# RX_Schematics.net
KiCad netlist of a schematic drawn in Altium Designer
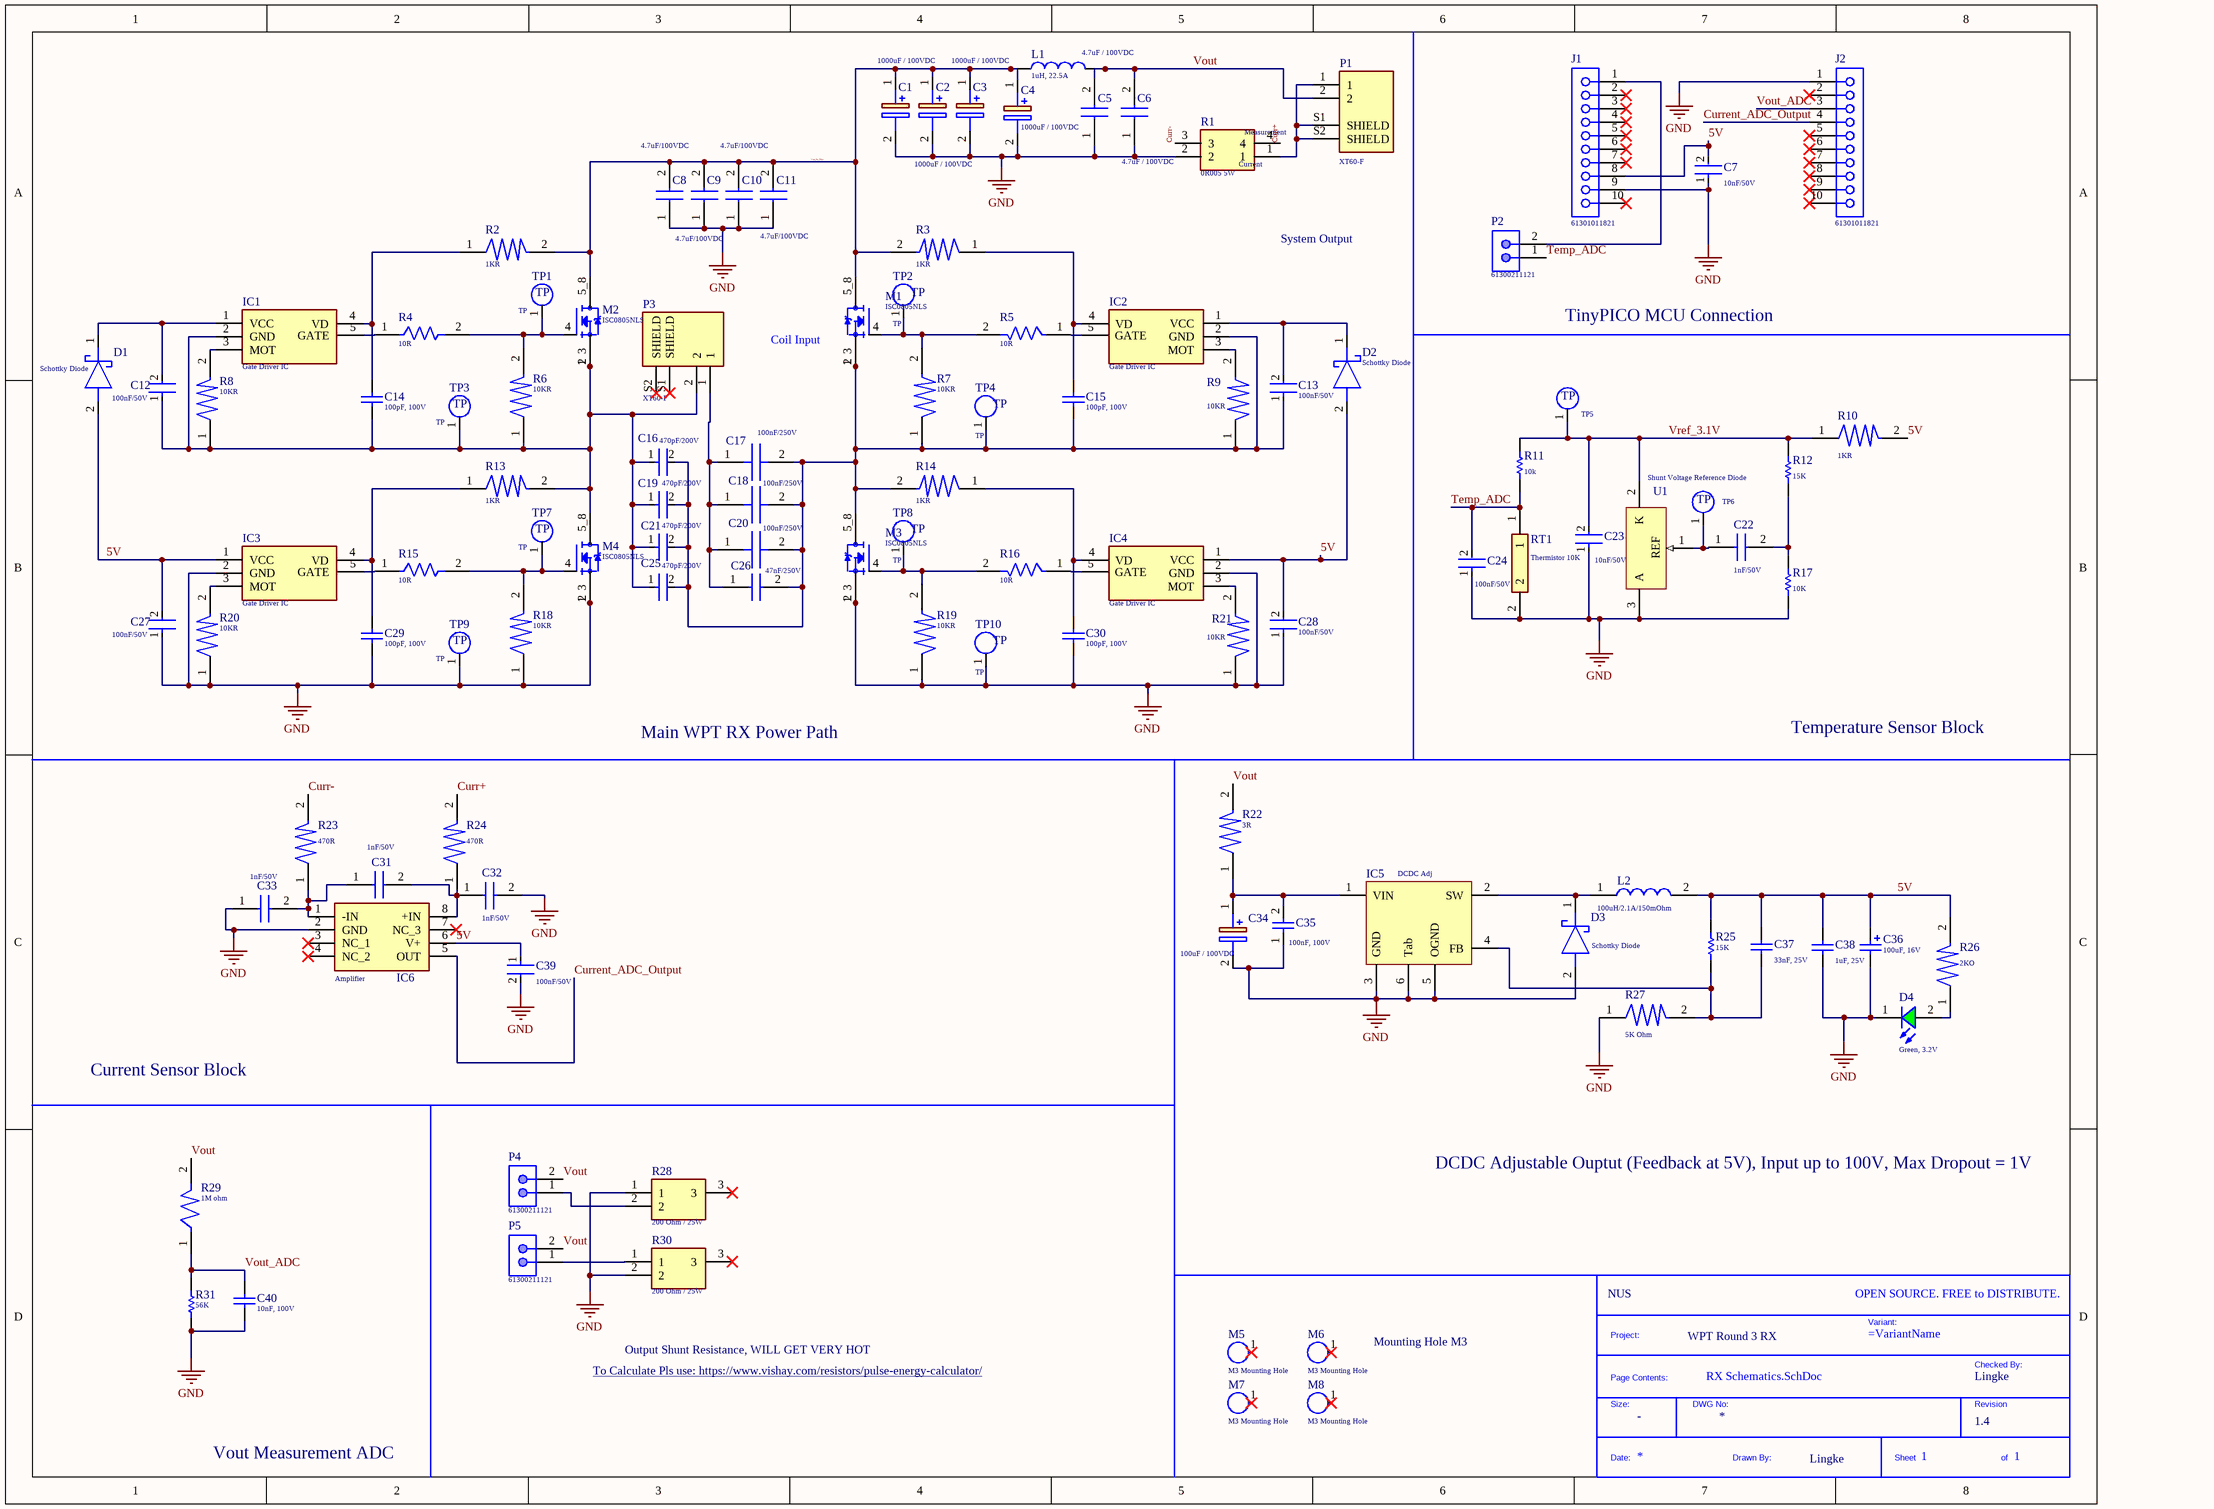
[diagram p0: RX Schematics.SchDoc]

(export (version "E")
  (design (tool "Eeschema 10.0.6"))
  (components
    (comp (ref "*1")
      (value "Title_Block")
      (description "Standard Title Block.")
      (fields
        (field (name "PROJECT NAME") "WPT Round 3 RX")
        (field (name "COMPANY") "NUS")
        (field (name "DRAWN BY") "Lingke")
        (field (name "REVISION") "1.4")
        (field (name "DWG NO") "*")
        (field (name "SIZE") "-")
        (field (name "CHECKED BY") "Lingke")
      )
      (libsource (lib "WPT NUS") (part "Title_Block"))
    )
    (comp (ref "C1")
      (value "1000uF / 100VDC")
      (footprint "CAPPRD750W80D1850H4200")
      (description "Capacitor Polarised")
      (fields
        (field (name "MANUFACTURER_PART_NUMBER") "UPW2A102MHD")
        (field (name "MOUSER PART NUMBER") "647-UPW2A102MHD")
      )
      (libsource (lib "WPT NUS") (part "UPW2A102MHD"))
    )
    (comp (ref "C2")
      (value "1000uF / 100VDC")
      (footprint "CAPPRD750W80D1850H4200")
      (description "Capacitor Polarised")
      (fields
        (field (name "MANUFACTURER_PART_NUMBER") "UPW2A102MHD")
        (field (name "MOUSER PART NUMBER") "647-UPW2A102MHD")
      )
      (libsource (lib "WPT NUS") (part "UPW2A102MHD"))
    )
    (comp (ref "C3")
      (value "1000uF / 100VDC")
      (footprint "CAPPRD750W80D1850H4200")
      (description "Capacitor Polarised")
      (fields
        (field (name "MANUFACTURER_PART_NUMBER") "UPW2A102MHD")
        (field (name "MOUSER PART NUMBER") "647-UPW2A102MHD")
      )
      (libsource (lib "WPT NUS") (part "UPW2A102MHD"))
    )
    (comp (ref "C4")
      (value "1000uF / 100VDC")
      (footprint "CAPPRD750W80D1850H4200")
      (description "Capacitor Polarised")
      (fields
        (field (name "MANUFACTURER_PART_NUMBER") "UPW2A102MHD")
        (field (name "MOUSER PART NUMBER") "647-UPW2A102MHD")
      )
      (libsource (lib "WPT NUS") (part "UPW2A102MHD"))
    )
    (comp (ref "C5")
      (value "4.7uF / 100VDC")
      (footprint "CAPC3225X280N")
      (description "Capacitor")
      (fields (field (name "MANUFACTURER_PART_NUMBER") "CL32B475KCVZNWE"))
      (libsource (lib "WPT NUS") (part "CL32B475KCVZNWE"))
    )
    (comp (ref "C6")
      (value "4.7uF / 100VDC")
      (footprint "CAPC3225X280N")
      (description "Capacitor")
      (fields (field (name "MANUFACTURER_PART_NUMBER") "CL32B475KCVZNWE"))
      (libsource (lib "WPT NUS") (part "CL32B475KCVZNWE"))
    )
    (comp (ref "C7")
      (value "10nF/50V")
      (footprint "0805 Capacitor")
      (libsource (lib "Symbol Library") (part "885012207092"))
    )
    (comp (ref "C8")
      (value "4.7uF/100VDC")
      (footprint "CAPC3225X280N")
      (fields
        (field (name "MOUSER2 PART NUMBER") "810-CNC6P1X7R2A475K2")
        (field (name "MANUFACTURER_PART_NUMBER") "CNC6P1X7R2A475K250AE")
      )
      (libsource (lib "WPT NUS") (part "CNC6P1X7R2A475K250AE"))
    )
    (comp (ref "C9")
      (value "4.7uF/100VDC")
      (footprint "CAPC3225X280N")
      (fields
        (field (name "MOUSER2 PART NUMBER") "810-CNC6P1X7R2A475K2")
        (field (name "MANUFACTURER_PART_NUMBER") "CNC6P1X7R2A475K250AE")
      )
      (libsource (lib "WPT NUS") (part "CNC6P1X7R2A475K250AE"))
    )
    (comp (ref "C10")
      (value "4.7uF/100VDC")
      (footprint "CAPC3225X280N")
      (fields
        (field (name "MOUSER2 PART NUMBER") "810-CNC6P1X7R2A475K2")
        (field (name "MANUFACTURER_PART_NUMBER") "CNC6P1X7R2A475K250AE")
      )
      (libsource (lib "WPT NUS") (part "CNC6P1X7R2A475K250AE"))
    )
    (comp (ref "C11")
      (value "4.7uF/100VDC")
      (footprint "CAPC3225X280N")
      (fields
        (field (name "MOUSER2 PART NUMBER") "810-CNC6P1X7R2A475K2")
        (field (name "MANUFACTURER_PART_NUMBER") "CNC6P1X7R2A475K250AE")
      )
      (libsource (lib "WPT NUS") (part "CNC6P1X7R2A475K250AE"))
    )
    (comp (ref "C12")
      (value "100nF/50V")
      (footprint "0805 Capacitor")
      (libsource (lib "WPT NUS") (part "885012207098"))
    )
    (comp (ref "C13")
      (value "100nF/50V")
      (footprint "0805 Capacitor")
      (libsource (lib "WPT NUS") (part "885012207098"))
    )
    (comp (ref "C14")
      (value "100pF, 100V")
      (footprint "WCAP-CSGP_0805_H=0.6mm_Reflow")
      (description "WCAP-CSGP Multilayer Ceramic Chip Capacitor, General Purpose, size 0805, NP0, 100pF, 100V")
      (fields
        (field (name "MANUFACTURER PART NUMBER") "885012007082")
        (field (name "MANUFACTURER") "Wurth Elektronik")
      )
      (libsource (lib "Altium_WCAP-CSGP (rev21d)") (part "885012007082"))
    )
    (comp (ref "C15")
      (value "100pF, 100V")
      (footprint "WCAP-CSGP_0805_H=0.6mm_Reflow")
      (description "WCAP-CSGP Multilayer Ceramic Chip Capacitor, General Purpose, size 0805, NP0, 100pF, 100V")
      (fields
        (field (name "MANUFACTURER PART NUMBER") "885012007082")
        (field (name "MANUFACTURER") "Wurth Elektronik")
      )
      (libsource (lib "Altium_WCAP-CSGP (rev21d)") (part "885012007082"))
    )
    (comp (ref "C16")
      (value "470pF/200V")
      (footprint "FP-C1206C-EB-MFG")
      (description "CAP CER 470PF 200V 10% NP0 1206")
      (fields
        (field (name "OCTOPART") "https://octopart.com/c1206c471k2gactu-kemet-3658280")
        (field (name "TOLERANCE") "0.1")
      )
      (libsource (lib "WPT NUS") (part "C1206C471K2GACTU"))
    )
    (comp (ref "C17")
      (value "100nF/250V")
      (footprint "CAPC4532X220N")
      (fields (field (name "MANUFACTURER_PART_NUMBER") "C1812C104JAGACAUTO"))
      (libsource (lib "WPT NUS") (part "C1812C104JAGACAUTO"))
    )
    (comp (ref "C18")
      (value "100nF/250V")
      (footprint "CAPC4532X220N")
      (fields (field (name "MANUFACTURER_PART_NUMBER") "C1812C104JAGACAUTO"))
      (libsource (lib "WPT NUS") (part "C1812C104JAGACAUTO"))
    )
    (comp (ref "C19")
      (value "470pF/200V")
      (footprint "FP-C1206C-EB-MFG")
      (description "CAP CER 470PF 200V 10% NP0 1206")
      (fields
        (field (name "OCTOPART") "https://octopart.com/c1206c471k2gactu-kemet-3658280")
        (field (name "TOLERANCE") "0.1")
      )
      (libsource (lib "WPT NUS") (part "C1206C471K2GACTU"))
    )
    (comp (ref "C20")
      (value "100nF/250V")
      (footprint "CAPC4532X220N")
      (fields (field (name "MANUFACTURER_PART_NUMBER") "C1812C104JAGACAUTO"))
      (libsource (lib "WPT NUS") (part "C1812C104JAGACAUTO"))
    )
    (comp (ref "C21")
      (value "470pF/200V")
      (footprint "FP-C1206C-EB-MFG")
      (description "CAP CER 470PF 200V 10% NP0 1206")
      (fields
        (field (name "OCTOPART") "https://octopart.com/c1206c471k2gactu-kemet-3658280")
        (field (name "TOLERANCE") "0.1")
      )
      (libsource (lib "WPT NUS") (part "C1206C471K2GACTU"))
    )
    (comp (ref "C22")
      (value "1nF/50V")
      (footprint "SamacSys:CAPC2012X90N")
      (fields (field (name "MANUFACTURER_PART_NUMBER") "885012207086"))
      (libsource (lib "Symbol Library") (part "885012207086"))
    )
    (comp (ref "C23")
      (value "10nF/50V")
      (footprint "0805 Capacitor")
      (libsource (lib "Symbol Library") (part "885012207092"))
    )
    (comp (ref "C24")
      (value "100nF/50V")
      (footprint "0805 Capacitor")
      (libsource (lib "Symbol Library") (part "885012207098"))
    )
    (comp (ref "C25")
      (value "470pF/200V")
      (footprint "FP-C1206C-EB-MFG")
      (description "CAP CER 470PF 200V 10% NP0 1206")
      (fields
        (field (name "OCTOPART") "https://octopart.com/c1206c471k2gactu-kemet-3658280")
        (field (name "TOLERANCE") "0.1")
      )
      (libsource (lib "WPT NUS") (part "C1206C471K2GACTU"))
    )
    (comp (ref "C26")
      (value "47nF/250V")
      (footprint "CAPC4532X350N")
      (description "Capacitor\r\n47nF/250V \r\nC0G")
      (fields (field (name "MANUFACTURER_PART_NUMBER") "C4532C0G2E473J320KA"))
      (libsource (lib "WPT NUS") (part "C4532C0G2E473J320KA"))
    )
    (comp (ref "C27")
      (value "100nF/50V")
      (footprint "0805 Capacitor")
      (libsource (lib "WPT NUS") (part "885012207098"))
    )
    (comp (ref "C28")
      (value "100nF/50V")
      (footprint "0805 Capacitor")
      (libsource (lib "WPT NUS") (part "885012207098"))
    )
    (comp (ref "C29")
      (value "100pF, 100V")
      (footprint "WCAP-CSGP_0805_H=0.6mm_Reflow")
      (description "WCAP-CSGP Multilayer Ceramic Chip Capacitor, General Purpose, size 0805, NP0, 100pF, 100V")
      (fields
        (field (name "MANUFACTURER PART NUMBER") "885012007082")
        (field (name "MANUFACTURER") "Wurth Elektronik")
      )
      (libsource (lib "Altium_WCAP-CSGP (rev21d)") (part "885012007082"))
    )
    (comp (ref "C30")
      (value "100pF, 100V")
      (footprint "WCAP-CSGP_0805_H=0.6mm_Reflow")
      (description "WCAP-CSGP Multilayer Ceramic Chip Capacitor, General Purpose, size 0805, NP0, 100pF, 100V")
      (fields
        (field (name "MANUFACTURER PART NUMBER") "885012007082")
        (field (name "MANUFACTURER") "Wurth Elektronik")
      )
      (libsource (lib "Altium_WCAP-CSGP (rev21d)") (part "885012007082"))
    )
    (comp (ref "C31")
      (value "1nF/50V")
      (footprint "SamacSys:CAPC2012X90N")
      (fields (field (name "MANUFACTURER_PART_NUMBER") "885012207086"))
      (libsource (lib "Symbol Library") (part "885012207086"))
    )
    (comp (ref "C32")
      (value "1nF/50V")
      (footprint "SamacSys:CAPC2012X90N")
      (fields (field (name "MANUFACTURER_PART_NUMBER") "885012207086"))
      (libsource (lib "Symbol Library") (part "885012207086"))
    )
    (comp (ref "C33")
      (value "1nF/50V")
      (footprint "SamacSys:CAPC2012X90N")
      (fields (field (name "MANUFACTURER_PART_NUMBER") "885012207086"))
      (libsource (lib "Symbol Library") (part "885012207086"))
    )
    (comp (ref "C34")
      (value "100uF / 100VDC")
      (footprint "CAPPRD500W60D1000H2200")
      (description "Capacitor Polarised")
      (fields
        (field (name "MANUFACTURER_PART_NUMBER") "ESH107M100AH4AA")
        (field (name "MOUSER PART NUMBER") "80-ESH107M100AH4AA")
      )
      (libsource (lib "WPT NUS") (part "ESH107M100AH4AA"))
    )
    (comp (ref "C35")
      (value "100nF, 100V")
      (footprint "WCAP-CSGP_0805_H=1.25mm")
      (description "WCAP-CSGP Multilayer Ceramic Chip Capacitor, General Purpose, size 0805, X7R, 100nF, 100V")
      (fields
        (field (name "MANUFACTURER PART NUMBER") "885012207128")
        (field (name "MANUFACTURER") "Wurth Elektronik")
      )
      (libsource (lib "Symbol Library") (part "885012207128"))
    )
    (comp (ref "C36")
      (value "100uF, 16V")
      (footprint "WCAP-ASLI_D6.3H5.5")
      (description "WCAP-ASLI Aluminum Electrolytic Capacitor, V-Chip, SMT, D6.3xH5.5mm, 100uF, 16V")
      (fields
        (field (name "MANUFACTURER PART NUMBER") "865080343009")
        (field (name "MANUFACTURER") "Wurth Elektronik")
      )
      (libsource (lib "Altium_WCAP-ASLI (rev20b) (1)") (part "865080343009"))
    )
    (comp (ref "C37")
      (value "33nF, 25V")
      (footprint "WCAP-CSGP_0805_H=0.8mm_Reflow")
      (description "WCAP-CSGP Multilayer Ceramic Chip Capacitor, General Purpose, size 0805, X7R, 33nF, 25V")
      (fields
        (field (name "MANUFACTURER PART NUMBER") "885012207069")
        (field (name "MANUFACTURER") "Wurth Elektronik")
      )
      (libsource (lib "Altium_WCAP-CSGP (rev21d)") (part "885012207069"))
    )
    (comp (ref "C38")
      (value "1uF, 25V")
      (footprint "WCAP-CSGP_0805_H=1.25mm")
      (description "WCAP-CSGP Multilayer Ceramic Chip Capacitor, General Purpose, size 0805, X7R, 1uF, 25V")
      (fields
        (field (name "MANUFACTURER PART NUMBER") "885012207078")
        (field (name "MANUFACTURER") "Wurth Elektronik")
      )
      (libsource (lib "Altium_WCAP-CSGP (rev21d)") (part "885012207078"))
    )
    (comp (ref "C39")
      (value "100nF/50V")
      (footprint "0805 Capacitor")
      (libsource (lib "Symbol Library") (part "885012207098"))
    )
    (comp (ref "C40")
      (value "10nF, 100V")
      (footprint "WCAP-CSGP_0805_H=0.8mm_Reflow")
      (description "WCAP-CSGP Multilayer Ceramic Chip Capacitor, General Purpose, size 0805, X7R, 10nF, 100V")
      (fields
        (field (name "MANUFACTURER PART NUMBER") "885012207122")
        (field (name "MANUFACTURER") "Wurth Elektronik")
      )
      (libsource (lib "Altium_WCAP-CSGP (rev21d)") (part "885012207122"))
    )
    (comp (ref "D1")
      (value "Schottky Diode")
      (footprint "RB400VAM50TR")
      (fields
        (field (name "MOUSER2 PART NUMBER") "755-RB400VAM-50TR")
        (field (name "MANUFACTURER_PART_NUMBER") "RB400VAM-50TR")
      )
      (libsource (lib "WPT NUS") (part "RB400VAM-50TR"))
    )
    (comp (ref "D2")
      (value "Schottky Diode")
      (footprint "RB400VAM50TR")
      (fields
        (field (name "MOUSER2 PART NUMBER") "755-RB400VAM-50TR")
        (field (name "MANUFACTURER_PART_NUMBER") "RB400VAM-50TR")
      )
      (libsource (lib "") (part "RB400VAM-50TR_1"))
    )
    (comp (ref "D3")
      (value "Schottky Diode")
      (footprint "SamacSys:DIONM8059X265N")
      (fields (field (name "MANUFACTURER_PART_NUMBER") "S310") (field (name "MOUSER PART NUMBER") "512-S310"))
      (libsource (lib "Symbol Library") (part "S310"))
    )
    (comp (ref "D4")
      (value "Green, 3.2V")
      (footprint "WL-SMCW_0805")
      (description "WL-SMCW SMT Mono-color Chip LED Waterclear, size 0805, Green, 3.2V, 140deg")
      (fields (field (name "PART NUMBER") "150080GS75000") (field (name "PUBLISHER") "Wurth Elektronik"))
      (libsource (lib "Altium_WL-SMCW (rev20a)") (part "150080GS75000"))
    )
    (comp (ref "IC1")
      (value "Gate Driver IC")
      (footprint "SOT95P280X145-5N")
      (fields (field (name "MANUFACTURER_PART_NUMBER") "IR1161LTRPBF"))
      (libsource (lib "") (part "IR1161LTRPBF_1"))
    )
    (comp (ref "IC2")
      (value "Gate Driver IC")
      (footprint "SOT95P280X145-5N")
      (fields (field (name "MANUFACTURER_PART_NUMBER") "IR1161LTRPBF"))
      (libsource (lib "WPT NUS") (part "IR1161LTRPBF"))
    )
    (comp (ref "IC3")
      (value "Gate Driver IC")
      (footprint "SOT95P280X145-5N")
      (fields (field (name "MANUFACTURER_PART_NUMBER") "IR1161LTRPBF"))
      (libsource (lib "") (part "IR1161LTRPBF_1"))
    )
    (comp (ref "IC4")
      (value "Gate Driver IC")
      (footprint "SOT95P280X145-5N")
      (fields (field (name "MANUFACTURER_PART_NUMBER") "IR1161LTRPBF"))
      (libsource (lib "WPT NUS") (part "IR1161LTRPBF"))
    )
    (comp (ref "IC5")
      (value "DCDC Adj")
      (footprint "TO-263-5")
      (libsource (lib "Symbol Library") (part "XL7035E1"))
    )
    (comp (ref "IC6")
      (value "Amplifier")
      (footprint "SamacSys:SOIC127P600X175-8N")
      (description "Integrated Circuit Amplifier")
      (fields (field (name "MANUFACTURER_PART_NUMBER") "AD8215YRZ"))
      (libsource (lib "Symbol Library") (part "AD8215YRZ"))
    )
    (comp (ref "J1")
      (value "61301011821")
      (footprint "61301011821")
      (description "WR-PHD Socket Header, THT, pitch 2.54mm, Single Row, Vertical, 10p")
      (fields (field (name "MANUFACTURER") "Wurth Elektronik"))
      (libsource (lib "Altium_WR-PHD (rev20a)") (part "61301011821"))
    )
    (comp (ref "J2")
      (value "61301011821")
      (footprint "61301011821")
      (description "WR-PHD Socket Header, THT, pitch 2.54mm, Single Row, Vertical, 10p")
      (fields (field (name "MANUFACTURER") "Wurth Elektronik"))
      (libsource (lib "Altium_WR-PHD (rev20a)") (part "61301011821"))
    )
    (comp (ref "L1")
      (value "1uH, 22.5A")
      (footprint "7847227010")
      (description "WE-RCIS SMT Rod Core Inductor, 1uH, 22.5A")
      (fields
        (field (name "MANUFACTURER PART NUMBER") "7847227010")
        (field (name "MANUFACTURER") "Wurth Elektronik")
      )
      (libsource (lib "Altium_WE-RCIS (rev21a)") (part "7847227010"))
    )
    (comp (ref "L2")
      (value "100uH/2.1A/150mOhm")
      (footprint "SamacSys:INDPM125125X800N")
      (description "Inductor")
      (fields
        (field (name "MANUFACTURER_PART_NUMBER") "SRR1280-101M")
        (field (name "MOUSER PART NUMBER") "652-SRR1280-101M")
      )
      (libsource (lib "Symbol Library") (part "SRR1280-101M"))
    )
    (comp (ref "M1")
      (value "ISC0805NLS")
      (footprint "PG-TDSON-8")
      (description "N-Channel 100V 71A 72")
      (fields (field (name "MP") "BSC010NE2LSI"))
      (libsource (lib "Symbol Library") (part "ISC0805NLS"))
    )
    (comp (ref "M2")
      (value "ISC0805NLS")
      (footprint "PG-TDSON-8")
      (description "N-Channel 100V 71A 72")
      (fields (field (name "MP") "BSC010NE2LSI"))
      (libsource (lib "Symbol Library") (part "ISC0805NLS"))
    )
    (comp (ref "M3")
      (value "ISC0805NLS")
      (footprint "PG-TDSON-8")
      (description "N-Channel 100V 71A 72")
      (fields (field (name "MP") "BSC010NE2LSI"))
      (libsource (lib "Symbol Library") (part "ISC0805NLS"))
    )
    (comp (ref "M4")
      (value "ISC0805NLS")
      (footprint "PG-TDSON-8")
      (description "N-Channel 100V 71A 72")
      (fields (field (name "MP") "BSC010NE2LSI"))
      (libsource (lib "Symbol Library") (part "ISC0805NLS"))
    )
    (comp (ref "M5")
      (value "M3 Mounting Hole")
      (footprint "M3 Hole")
      (libsource (lib "Symbol Library") (part "M3_Mounting_hole"))
    )
    (comp (ref "M6")
      (value "M3 Mounting Hole")
      (footprint "M3 Hole")
      (libsource (lib "Symbol Library") (part "M3_Mounting_hole"))
    )
    (comp (ref "M7")
      (value "M3 Mounting Hole")
      (footprint "M3 Hole")
      (libsource (lib "Symbol Library") (part "M3_Mounting_hole"))
    )
    (comp (ref "M8")
      (value "M3 Mounting Hole")
      (footprint "M3 Hole")
      (libsource (lib "Symbol Library") (part "M3_Mounting_hole"))
    )
    (comp (ref "P1")
      (value "XT60-F")
      (footprint "AMASS_XT60PW-F")
      (description "Socket DC Supply Connector Female")
      (fields (field (name "MP") "XT60PW-F") (field (name "MF") "AMASS"))
      (libsource (lib "WPT NUS") (part "XT60PW-F"))
    )
    (comp (ref "P2")
      (value "61300211121")
      (footprint "61300211121")
      (description "WR-PHD Pin Header, THT, pitch 2.54mm, Single Row, Vertical, 2p")
      (fields (field (name "MANUFACTURER") "Wurth Elektronik"))
      (libsource (lib "Altium_WR-PHD (rev20a)") (part "61300211121"))
    )
    (comp (ref "P3")
      (value "XT60-F")
      (footprint "AMASS_XT60PW-F")
      (description "Socket DC Supply Connector Female")
      (fields (field (name "MP") "XT60PW-F") (field (name "MF") "AMASS"))
      (libsource (lib "WPT NUS") (part "XT60PW-F"))
    )
    (comp (ref "P4")
      (value "61300211121")
      (footprint "61300211121")
      (description "WR-PHD Pin Header, THT, pitch 2.54mm, Single Row, Vertical, 2p")
      (fields (field (name "MANUFACTURER") "Wurth Elektronik"))
      (libsource (lib "Altium_WR-PHD (rev20a)") (part "61300211121"))
    )
    (comp (ref "P5")
      (value "61300211121")
      (footprint "61300211121")
      (description "WR-PHD Pin Header, THT, pitch 2.54mm, Single Row, Vertical, 2p")
      (fields (field (name "MANUFACTURER") "Wurth Elektronik"))
      (libsource (lib "Altium_WR-PHD (rev20a)") (part "61300211121"))
    )
    (comp (ref "R1")
      (value "0R005 5W")
      (footprint "FC4L110R005FER")
      (description "Resistor 0R005 5W")
      (fields (field (name "MANUFACTURER_PART_NUMBER") "FC4L110R005FER"))
      (libsource (lib "WPT NUS") (part "FC4L110R005FER"))
    )
    (comp (ref "R2")
      (value "1KR")
      (footprint "FP-CRCW0805-e3-MFG")
      (description "Resistor 1k Ohm")
      (libsource (lib "WPT NUS") (part "CRCW08051K00FKEA"))
    )
    (comp (ref "R3")
      (value "1KR")
      (footprint "FP-CRCW0805-e3-MFG")
      (description "Resistor 1k Ohm")
      (libsource (lib "WPT NUS") (part "CRCW08051K00FKEA"))
    )
    (comp (ref "R4")
      (value "10R")
      (footprint "FP-CRCW1206-e3-IPC_A")
      (description "RES Thick Film, 10Ω, 1%, 0.25W, 100ppm/°C, 1206\r\nMOSFET Gate Resistor 10Ohm")
      (fields (field (name "TOLERANCE") "1%"))
      (libsource (lib "WPT NUS") (part "CRCW120610R0FKEA"))
    )
    (comp (ref "R5")
      (value "10R")
      (footprint "FP-CRCW1206-e3-IPC_A")
      (description "RES Thick Film, 10Ω, 1%, 0.25W, 100ppm/°C, 1206\r\nMOSFET Gate Resistor 10Ohm")
      (fields (field (name "TOLERANCE") "1%"))
      (libsource (lib "WPT NUS") (part "CRCW120610R0FKEA"))
    )
    (comp (ref "R6")
      (value "10KR")
      (footprint "FP-CRCW0805-e3-MFG")
      (description "Resistor 10K Ohm")
      (libsource (lib "WPT NUS") (part "CRCW080510K0FKEA"))
    )
    (comp (ref "R7")
      (value "10KR")
      (footprint "FP-CRCW0805-e3-MFG")
      (description "Resistor 10K Ohm")
      (libsource (lib "WPT NUS") (part "CRCW080510K0FKEA"))
    )
    (comp (ref "R8")
      (value "10KR")
      (footprint "FP-CRCW0805-e3-MFG")
      (description "Resistor 10K Ohm")
      (libsource (lib "WPT NUS") (part "CRCW080510K0FKEA"))
    )
    (comp (ref "R9")
      (value "10KR")
      (footprint "FP-CRCW0805-e3-MFG")
      (description "Resistor 10K Ohm")
      (libsource (lib "WPT NUS") (part "CRCW080510K0FKEA"))
    )
    (comp (ref "R10")
      (value "1KR")
      (footprint "FP-CRCW0805-e3-MFG")
      (description "Resistor 1k Ohm")
      (libsource (lib "Symbol Library") (part "CRCW08051K00FKEA"))
    )
    (comp (ref "R11")
      (value "10k")
      (footprint "0805 Resistor")
      (description "High Presition and High reliability 10K Ohm Resistor")
      (libsource (lib "Symbol Library") (part "ERA-6ARB103V"))
    )
    (comp (ref "R12")
      (value "15K")
      (footprint "0805 Resistor")
      (description "High Presicion 15K Ohm")
      (libsource (lib "Symbol Library") (part "ERA-6ARW153V"))
    )
    (comp (ref "R13")
      (value "1KR")
      (footprint "FP-CRCW0805-e3-MFG")
      (description "Resistor 1k Ohm")
      (libsource (lib "WPT NUS") (part "CRCW08051K00FKEA"))
    )
    (comp (ref "R14")
      (value "1KR")
      (footprint "FP-CRCW0805-e3-MFG")
      (description "Resistor 1k Ohm")
      (libsource (lib "WPT NUS") (part "CRCW08051K00FKEA"))
    )
    (comp (ref "R15")
      (value "10R")
      (footprint "FP-CRCW1206-e3-IPC_A")
      (description "RES Thick Film, 10Ω, 1%, 0.25W, 100ppm/°C, 1206\r\nMOSFET Gate Resistor 10Ohm")
      (fields (field (name "TOLERANCE") "1%"))
      (libsource (lib "WPT NUS") (part "CRCW120610R0FKEA"))
    )
    (comp (ref "R16")
      (value "10R")
      (footprint "FP-CRCW1206-e3-IPC_A")
      (description "RES Thick Film, 10Ω, 1%, 0.25W, 100ppm/°C, 1206\r\nMOSFET Gate Resistor 10Ohm")
      (fields (field (name "TOLERANCE") "1%"))
      (libsource (lib "WPT NUS") (part "CRCW120610R0FKEA"))
    )
    (comp (ref "R17")
      (value "10K")
      (footprint "0805 Resistor")
      (description "High Presicion 10K Ohm")
      (libsource (lib "Symbol Library") (part "CRCW080510K0FKEB"))
    )
    (comp (ref "R18")
      (value "10KR")
      (footprint "FP-CRCW0805-e3-MFG")
      (description "Resistor 10K Ohm")
      (libsource (lib "WPT NUS") (part "CRCW080510K0FKEA"))
    )
    (comp (ref "R19")
      (value "10KR")
      (footprint "FP-CRCW0805-e3-MFG")
      (description "Resistor 10K Ohm")
      (libsource (lib "WPT NUS") (part "CRCW080510K0FKEA"))
    )
    (comp (ref "R20")
      (value "10KR")
      (footprint "FP-CRCW0805-e3-MFG")
      (description "Resistor 10K Ohm")
      (libsource (lib "WPT NUS") (part "CRCW080510K0FKEA"))
    )
    (comp (ref "R21")
      (value "10KR")
      (footprint "FP-CRCW0805-e3-MFG")
      (description "Resistor 10K Ohm")
      (libsource (lib "WPT NUS") (part "CRCW080510K0FKEA"))
    )
    (comp (ref "R22")
      (value "3R")
      (footprint "1206_Resistor")
      (description "Resistor 3 Ohm")
      (libsource (lib "WPT NUS") (part "CRCW12063R00FKEAHP"))
    )
    (comp (ref "R23")
      (value "470R")
      (footprint "FP-CRCW0805-e3-MFG")
      (description "Resistor 470 Ohm")
      (libsource (lib "Symbol Library") (part "CRCW0805470RFKEB"))
    )
    (comp (ref "R24")
      (value "470R")
      (footprint "FP-CRCW0805-e3-MFG")
      (description "Resistor 470 Ohm")
      (libsource (lib "Symbol Library") (part "CRCW0805470RFKEB"))
    )
    (comp (ref "R25")
      (value "15K")
      (footprint "0805 Resistor")
      (description "15K Ohm Resistor")
      (libsource (lib "WPT NUS") (part "ERA-6AED153V"))
    )
    (comp (ref "R26")
      (value "2KO")
      (footprint "FP-CRCW0805-e3-MFG")
      (description "RES Thick Film, 2kΩ, 1%, 0.125W, 100ppm/°C, 0805")
      (fields (field (name "TOLERANCE") "1%"))
      (libsource (lib "Symbol Library") (part "CRCW08052K00FKEB"))
    )
    (comp (ref "R27")
      (value "5K Ohm")
      (footprint "FP-CRCW0805-e3-MFG")
      (description "Resistor 5K Ohm")
      (libsource (lib "Symbol Library") (part "CRCW08055K00FKTA"))
    )
    (comp (ref "R28")
      (value "200 Ohm / 25W")
      (footprint "PWR163S253000FE")
      (description "Resistor 200 Ohm / 25W")
      (fields (field (name "MANUFACTURER_PART_NUMBER") "PWR163S-25-3000FE"))
      (libsource (lib "WPT NUS") (part "PWR163S-25-2000FE"))
    )
    (comp (ref "R29")
      (value "1M ohm")
      (footprint "FP-CRCW0805-e3-MFG")
      (description "RES Thick Film, 1MΩ, 1%, 0.125W, 100ppm/°C, 0805\r\n1M Ohm Resistor")
      (fields (field (name "TOLERANCE") "1%"))
      (libsource (lib "WPT NUS") (part "CRCW08051M00FKEA"))
    )
    (comp (ref "R30")
      (value "200 Ohm / 25W")
      (footprint "PWR163S253000FE")
      (description "Resistor 200 Ohm / 25W")
      (fields (field (name "MANUFACTURER_PART_NUMBER") "PWR163S-25-3000FE"))
      (libsource (lib "WPT NUS") (part "PWR163S-25-2000FE"))
    )
    (comp (ref "R31")
      (value "56K")
      (footprint "0805 Resistor")
      (description "56K Ohm Resistor")
      (libsource (lib "WPT NUS") (part "ERJ-6ENF5622V"))
    )
    (comp (ref "RT1")
      (value "Thermistor 10K")
      (footprint "SamacSys:THRMC2012X95N")
      (description "Thermistor 10Kohm B Parameter: 3950k")
      (fields (field (name "MANUFACTURER_PART_NUMBER") "NTCS0805E3103HMT"))
      (libsource (lib "Symbol Library") (part "NTCS0805E3103HMT"))
    )
    (comp (ref "TP1")
      (value "TP")
      (footprint "Test Point")
      (description "Test Point 1mm by 1mm")
      (libsource (lib "WPT NUS") (part "Test Point"))
    )
    (comp (ref "TP2")
      (value "TP")
      (footprint "Test Point")
      (description "Test Point 1mm by 1mm")
      (libsource (lib "WPT NUS") (part "Test Point"))
    )
    (comp (ref "TP3")
      (value "TP")
      (footprint "Test Point")
      (description "Test Point 1mm by 1mm")
      (libsource (lib "WPT NUS") (part "Test Point"))
    )
    (comp (ref "TP4")
      (value "TP")
      (footprint "Test Point")
      (description "Test Point 1mm by 1mm")
      (libsource (lib "WPT NUS") (part "Test Point"))
    )
    (comp (ref "TP5")
      (value "TP")
      (footprint "Test Point")
      (description "Test Point 1mm by 1mm")
      (libsource (lib "Symbol Library") (part "Test Point"))
    )
    (comp (ref "TP6")
      (value "TP")
      (footprint "Test Point")
      (description "Test Point 1mm by 1mm")
      (libsource (lib "Symbol Library") (part "Test Point"))
    )
    (comp (ref "TP7")
      (value "TP")
      (footprint "Test Point")
      (description "Test Point 1mm by 1mm")
      (libsource (lib "WPT NUS") (part "Test Point"))
    )
    (comp (ref "TP8")
      (value "TP")
      (footprint "Test Point")
      (description "Test Point 1mm by 1mm")
      (libsource (lib "WPT NUS") (part "Test Point"))
    )
    (comp (ref "TP9")
      (value "TP")
      (footprint "Test Point")
      (description "Test Point 1mm by 1mm")
      (libsource (lib "WPT NUS") (part "Test Point"))
    )
    (comp (ref "TP10")
      (value "TP")
      (footprint "Test Point")
      (description "Test Point 1mm by 1mm")
      (libsource (lib "WPT NUS") (part "Test Point"))
    )
    (comp (ref "U1")
      (value "Shunt Voltage Reference Diode")
      (footprint "SOT23-3_N")
      (description "Shunt voltage reference, adjustable, 1.24 to 10V, 0.5% precision, 3-Pin SOT23-3L, Tape and Reel")
      (libsource (lib "Symbol Library") (part "TS432AILT"))
    )
  )
  (nets
    (net (code "1") (name "/5V") (class "Default")
      (node (ref "C27") (pin "2") (pinfunction "2_2") (pintype "passive"))
      (node (ref "C28") (pin "2") (pinfunction "2_2") (pintype "passive"))
      (node (ref "C36") (pin "1") (pinfunction "P_1") (pintype "passive"))
      (node (ref "C37") (pin "2") (pinfunction "2_2") (pintype "passive"))
      (node (ref "C38") (pin "2") (pinfunction "2_2") (pintype "passive"))
      (node (ref "C39") (pin "1") (pinfunction "1_1") (pintype "passive"))
      (node (ref "C7") (pin "2") (pinfunction "2_2") (pintype "passive"))
      (node (ref "D1") (pin "2") (pinfunction "A_2") (pintype "passive"))
      (node (ref "D2") (pin "2") (pinfunction "A_2") (pintype "passive"))
      (node (ref "IC3") (pin "1") (pinfunction "VCC_1") (pintype "passive"))
      (node (ref "IC4") (pin "1") (pinfunction "VCC_1") (pintype "passive"))
      (node (ref "IC6") (pin "6") (pinfunction "V+_6") (pintype "passive"))
      (node (ref "J1") (pin "8") (pinfunction "8_8") (pintype "passive"))
      (node (ref "L2") (pin "2") (pinfunction "2_2") (pintype "passive"))
      (node (ref "R10") (pin "2") (pinfunction "2_2") (pintype "passive"))
      (node (ref "R25") (pin "2") (pinfunction "2_2") (pintype "passive"))
      (node (ref "R26") (pin "2") (pinfunction "2_2") (pintype "passive"))
    )
    (net (code "2") (name "/Curr+") (class "Default")
      (node (ref "R1") (pin "4") (pinfunction "4_4") (pintype "passive"))
      (node (ref "R24") (pin "2") (pinfunction "2_2") (pintype "passive"))
    )
    (net (code "3") (name "/Curr-") (class "Default")
      (node (ref "R1") (pin "3") (pinfunction "3_3") (pintype "passive"))
      (node (ref "R23") (pin "2") (pinfunction "2_2") (pintype "passive"))
    )
    (net (code "4") (name "/Current_ADC_Output") (class "Default")
      (node (ref "IC6") (pin "5") (pinfunction "OUT_5") (pintype "passive"))
      (node (ref "J2") (pin "4") (pinfunction "4_4") (pintype "passive"))
    )
    (net (code "5") (name "/Temp_ADC") (class "Default")
      (node (ref "C24") (pin "2") (pinfunction "2_2") (pintype "passive"))
      (node (ref "P2") (pin "1") (pinfunction "1_1") (pintype "passive"))
      (node (ref "R11") (pin "1") (pinfunction "1_1") (pintype "passive"))
      (node (ref "RT1") (pin "1") (pinfunction "1_1") (pintype "passive"))
    )
    (net (code "6") (name "/Vout") (class "Default")
      (node (ref "C5") (pin "2") (pinfunction "2_2") (pintype "passive"))
      (node (ref "C6") (pin "2") (pinfunction "2_2") (pintype "passive"))
      (node (ref "L1") (pin "2") (pinfunction "2_2") (pintype "passive"))
      (node (ref "P1") (pin "2") (pinfunction "2_2") (pintype "passive"))
      (node (ref "P4") (pin "2") (pinfunction "2_2") (pintype "passive"))
      (node (ref "P5") (pin "2") (pinfunction "2_2") (pintype "passive"))
      (node (ref "R22") (pin "2") (pinfunction "2_2") (pintype "passive"))
      (node (ref "R29") (pin "2") (pinfunction "2_2") (pintype "passive"))
    )
    (net (code "7") (name "/Vout_ADC") (class "Default")
      (node (ref "C40") (pin "2") (pinfunction "2_2") (pintype "passive"))
      (node (ref "J2") (pin "3") (pinfunction "3_3") (pintype "passive"))
      (node (ref "R29") (pin "1") (pinfunction "1_1") (pintype "passive"))
      (node (ref "R31") (pin "2") (pinfunction "2_2") (pintype "passive"))
    )
    (net (code "8") (name "/Vout_Pre_Filter") (class "Default")
      (node (ref "C1") (pin "1") (pinfunction "+_1") (pintype "passive"))
      (node (ref "C10") (pin "2") (pinfunction "2_2") (pintype "passive"))
      (node (ref "C11") (pin "2") (pinfunction "2_2") (pintype "passive"))
      (node (ref "C2") (pin "1") (pinfunction "+_1") (pintype "passive"))
      (node (ref "C3") (pin "1") (pinfunction "+_1") (pintype "passive"))
      (node (ref "C4") (pin "1") (pinfunction "+_1") (pintype "passive"))
      (node (ref "C8") (pin "2") (pinfunction "2_2") (pintype "passive"))
      (node (ref "C9") (pin "2") (pinfunction "2_2") (pintype "passive"))
      (node (ref "L1") (pin "1") (pinfunction "1_1") (pintype "passive"))
      (node (ref "M1") (pin "5_8") (pinfunction "D_5_8") (pintype "passive"))
      (node (ref "M2") (pin "5_8") (pinfunction "D_5_8") (pintype "passive"))
      (node (ref "R2") (pin "2") (pinfunction "2_2") (pintype "passive"))
      (node (ref "R3") (pin "2") (pinfunction "2_2") (pintype "passive"))
    )
    (net (code "9") (name "/Vref_3.1V") (class "Default")
      (node (ref "C23") (pin "2") (pinfunction "2_2") (pintype "passive"))
      (node (ref "R10") (pin "1") (pinfunction "1_1") (pintype "passive"))
      (node (ref "R11") (pin "2") (pinfunction "2_2") (pintype "passive"))
      (node (ref "R12") (pin "2") (pinfunction "2_2") (pintype "passive"))
      (node (ref "TP5") (pin "1") (pinfunction "TP_1") (pintype "passive"))
      (node (ref "U1") (pin "2") (pinfunction "K_2") (pintype "passive"))
    )
    (net (code "10") (name "GND") (class "Default")
      (node (ref "C1") (pin "2") (pinfunction "-_2") (pintype "passive"))
      (node (ref "C10") (pin "1") (pinfunction "1_1") (pintype "passive"))
      (node (ref "C11") (pin "1") (pinfunction "1_1") (pintype "passive"))
      (node (ref "C2") (pin "2") (pinfunction "-_2") (pintype "passive"))
      (node (ref "C23") (pin "1") (pinfunction "1_1") (pintype "passive"))
      (node (ref "C24") (pin "1") (pinfunction "1_1") (pintype "passive"))
      (node (ref "C27") (pin "1") (pinfunction "1_1") (pintype "passive"))
      (node (ref "C28") (pin "1") (pinfunction "1_1") (pintype "passive"))
      (node (ref "C29") (pin "1") (pinfunction "1_1") (pintype "passive"))
      (node (ref "C3") (pin "2") (pinfunction "-_2") (pintype "passive"))
      (node (ref "C30") (pin "1") (pinfunction "1_1") (pintype "passive"))
      (node (ref "C32") (pin "2") (pinfunction "2_2") (pintype "passive"))
      (node (ref "C33") (pin "1") (pinfunction "1_1") (pintype "passive"))
      (node (ref "C34") (pin "2") (pinfunction "-_2") (pintype "passive"))
      (node (ref "C35") (pin "1") (pinfunction "1_1") (pintype "passive"))
      (node (ref "C36") (pin "2") (pinfunction "N_2") (pintype "passive"))
      (node (ref "C38") (pin "1") (pinfunction "1_1") (pintype "passive"))
      (node (ref "C39") (pin "2") (pinfunction "2_2") (pintype "passive"))
      (node (ref "C4") (pin "2") (pinfunction "-_2") (pintype "passive"))
      (node (ref "C40") (pin "1") (pinfunction "1_1") (pintype "passive"))
      (node (ref "C5") (pin "1") (pinfunction "1_1") (pintype "passive"))
      (node (ref "C6") (pin "1") (pinfunction "1_1") (pintype "passive"))
      (node (ref "C7") (pin "1") (pinfunction "1_1") (pintype "passive"))
      (node (ref "C8") (pin "1") (pinfunction "1_1") (pintype "passive"))
      (node (ref "C9") (pin "1") (pinfunction "1_1") (pintype "passive"))
      (node (ref "D3") (pin "2") (pinfunction "A_2") (pintype "passive"))
      (node (ref "D4") (pin "1") (pinfunction "K_1") (pintype "passive"))
      (node (ref "IC3") (pin "2") (pinfunction "GND_2") (pintype "passive"))
      (node (ref "IC4") (pin "2") (pinfunction "GND_2") (pintype "passive"))
      (node (ref "IC5") (pin "3") (pinfunction "GND_3") (pintype "passive"))
      (node (ref "IC5") (pin "5") (pinfunction "OGND_5") (pintype "passive"))
      (node (ref "IC5") (pin "6") (pinfunction "Tab_6") (pintype "passive"))
      (node (ref "IC6") (pin "2") (pinfunction "GND_2") (pintype "passive"))
      (node (ref "J1") (pin "9") (pinfunction "9_9") (pintype "passive"))
      (node (ref "J2") (pin "1") (pinfunction "1_1") (pintype "passive"))
      (node (ref "M3") (pin "1") (pinfunction "S_1") (pintype "passive"))
      (node (ref "M3") (pin "2") (pinfunction "S_2") (pintype "passive"))
      (node (ref "M3") (pin "3") (pinfunction "S_3") (pintype "passive"))
      (node (ref "M4") (pin "1") (pinfunction "S_1") (pintype "passive"))
      (node (ref "M4") (pin "2") (pinfunction "S_2") (pintype "passive"))
      (node (ref "M4") (pin "3") (pinfunction "S_3") (pintype "passive"))
      (node (ref "R1") (pin "2") (pinfunction "2_2") (pintype "passive"))
      (node (ref "R17") (pin "1") (pinfunction "1_1") (pintype "passive"))
      (node (ref "R18") (pin "1") (pinfunction "1_1") (pintype "passive"))
      (node (ref "R19") (pin "1") (pinfunction "1_1") (pintype "passive"))
      (node (ref "R20") (pin "1") (pinfunction "1_1") (pintype "passive"))
      (node (ref "R21") (pin "1") (pinfunction "1_1") (pintype "passive"))
      (node (ref "R27") (pin "1") (pinfunction "1_1") (pintype "passive"))
      (node (ref "R28") (pin "1") (pinfunction "1_1") (pintype "passive"))
      (node (ref "R30") (pin "2") (pinfunction "2_2") (pintype "passive"))
      (node (ref "R31") (pin "1") (pinfunction "1_1") (pintype "passive"))
      (node (ref "RT1") (pin "2") (pinfunction "2_2") (pintype "passive"))
      (node (ref "TP10") (pin "1") (pinfunction "TP_1") (pintype "passive"))
      (node (ref "TP9") (pin "1") (pinfunction "TP_1") (pintype "passive"))
      (node (ref "U1") (pin "3") (pinfunction "A_3") (pintype "passive"))
    )
    (net (code "11") (name "Net-(C17-Pad1)") (class "Default")
      (node (ref "C17") (pin "1") (pinfunction "1_1") (pintype "passive"))
      (node (ref "C18") (pin "1") (pinfunction "1_1") (pintype "passive"))
      (node (ref "C20") (pin "1") (pinfunction "1_1") (pintype "passive"))
      (node (ref "C26") (pin "1") (pinfunction "1_1") (pintype "passive"))
      (node (ref "P3") (pin "1") (pinfunction "1_1") (pintype "passive"))
    )
    (net (code "12") (name "Net-(C22-Pad2)") (class "Default")
      (node (ref "C22") (pin "2") (pinfunction "2_2") (pintype "passive"))
      (node (ref "R12") (pin "1") (pinfunction "1_1") (pintype "passive"))
      (node (ref "R17") (pin "2") (pinfunction "2_2") (pintype "passive"))
    )
    (net (code "13") (name "Net-(C34-+)") (class "Default")
      (node (ref "C34") (pin "1") (pinfunction "+_1") (pintype "passive"))
      (node (ref "C35") (pin "2") (pinfunction "2_2") (pintype "passive"))
      (node (ref "IC5") (pin "1") (pinfunction "VIN_1") (pintype "passive"))
      (node (ref "R22") (pin "1") (pinfunction "1_1") (pintype "passive"))
    )
    (net (code "14") (name "Net-(D1-K)") (class "Default")
      (node (ref "C12") (pin "2") (pinfunction "2_2") (pintype "passive"))
      (node (ref "D1") (pin "1") (pinfunction "K_1") (pintype "passive"))
      (node (ref "IC1") (pin "1") (pinfunction "VCC_1") (pintype "passive"))
    )
    (net (code "15") (name "Net-(D2-K)") (class "Default")
      (node (ref "C13") (pin "2") (pinfunction "2_2") (pintype "passive"))
      (node (ref "D2") (pin "1") (pinfunction "K_1") (pintype "passive"))
      (node (ref "IC2") (pin "1") (pinfunction "VCC_1") (pintype "passive"))
    )
    (net (code "16") (name "Net-(D3-K)") (class "Default")
      (node (ref "D3") (pin "1") (pinfunction "K_1") (pintype "passive"))
      (node (ref "IC5") (pin "2") (pinfunction "SW_2") (pintype "passive"))
      (node (ref "L2") (pin "1") (pinfunction "1_1") (pintype "passive"))
    )
    (net (code "17") (name "Net-(D4-A)") (class "Default")
      (node (ref "D4") (pin "2") (pinfunction "A_2") (pintype "passive"))
      (node (ref "R26") (pin "1") (pinfunction "1_1") (pintype "passive"))
    )
    (net (code "18") (name "Net-(IC1-GATE)") (class "Default")
      (node (ref "IC1") (pin "5") (pinfunction "GATE_5") (pintype "passive"))
      (node (ref "R4") (pin "1") (pinfunction "1_1") (pintype "passive"))
    )
    (net (code "19") (name "Net-(IC1-GND)") (class "Default")
      (node (ref "C12") (pin "1") (pinfunction "1_1") (pintype "passive"))
      (node (ref "C14") (pin "1") (pinfunction "1_1") (pintype "passive"))
      (node (ref "C16") (pin "1") (pinfunction "1_1") (pintype "passive"))
      (node (ref "C19") (pin "1") (pinfunction "1_1") (pintype "passive"))
      (node (ref "C21") (pin "1") (pinfunction "1_1") (pintype "passive"))
      (node (ref "C25") (pin "1") (pinfunction "1_1") (pintype "passive"))
      (node (ref "IC1") (pin "2") (pinfunction "GND_2") (pintype "passive"))
      (node (ref "M2") (pin "1") (pinfunction "S_1") (pintype "passive"))
      (node (ref "M2") (pin "2") (pinfunction "S_2") (pintype "passive"))
      (node (ref "M2") (pin "3") (pinfunction "S_3") (pintype "passive"))
      (node (ref "M4") (pin "5_8") (pinfunction "D_5_8") (pintype "passive"))
      (node (ref "P3") (pin "2") (pinfunction "2_2") (pintype "passive"))
      (node (ref "R13") (pin "2") (pinfunction "2_2") (pintype "passive"))
      (node (ref "R6") (pin "1") (pinfunction "1_1") (pintype "passive"))
      (node (ref "R8") (pin "1") (pinfunction "1_1") (pintype "passive"))
      (node (ref "TP3") (pin "1") (pinfunction "TP_1") (pintype "passive"))
    )
    (net (code "20") (name "Net-(IC1-MOT)") (class "Default")
      (node (ref "IC1") (pin "3") (pinfunction "MOT_3") (pintype "passive"))
      (node (ref "R8") (pin "2") (pinfunction "2_2") (pintype "passive"))
    )
    (net (code "21") (name "Net-(IC1-VD)") (class "Default")
      (node (ref "C14") (pin "2") (pinfunction "2_2") (pintype "passive"))
      (node (ref "IC1") (pin "4") (pinfunction "VD_4") (pintype "passive"))
      (node (ref "R2") (pin "1") (pinfunction "1_1") (pintype "passive"))
    )
    (net (code "22") (name "Net-(IC2-GATE)") (class "Default")
      (node (ref "IC2") (pin "5") (pinfunction "GATE_5") (pintype "passive"))
      (node (ref "R5") (pin "1") (pinfunction "1_1") (pintype "passive"))
    )
    (net (code "23") (name "Net-(IC2-GND)") (class "Default")
      (node (ref "C13") (pin "1") (pinfunction "1_1") (pintype "passive"))
      (node (ref "C15") (pin "1") (pinfunction "1_1") (pintype "passive"))
      (node (ref "C16") (pin "2") (pinfunction "2_2") (pintype "passive"))
      (node (ref "C17") (pin "2") (pinfunction "2_2") (pintype "passive"))
      (node (ref "C18") (pin "2") (pinfunction "2_2") (pintype "passive"))
      (node (ref "C19") (pin "2") (pinfunction "2_2") (pintype "passive"))
      (node (ref "C20") (pin "2") (pinfunction "2_2") (pintype "passive"))
      (node (ref "C21") (pin "2") (pinfunction "2_2") (pintype "passive"))
      (node (ref "C25") (pin "2") (pinfunction "2_2") (pintype "passive"))
      (node (ref "C26") (pin "2") (pinfunction "2_2") (pintype "passive"))
      (node (ref "IC2") (pin "2") (pinfunction "GND_2") (pintype "passive"))
      (node (ref "M1") (pin "1") (pinfunction "S_1") (pintype "passive"))
      (node (ref "M1") (pin "2") (pinfunction "S_2") (pintype "passive"))
      (node (ref "M1") (pin "3") (pinfunction "S_3") (pintype "passive"))
      (node (ref "M3") (pin "5_8") (pinfunction "D_5_8") (pintype "passive"))
      (node (ref "R14") (pin "2") (pinfunction "2_2") (pintype "passive"))
      (node (ref "R7") (pin "1") (pinfunction "1_1") (pintype "passive"))
      (node (ref "R9") (pin "1") (pinfunction "1_1") (pintype "passive"))
      (node (ref "TP4") (pin "1") (pinfunction "TP_1") (pintype "passive"))
    )
    (net (code "24") (name "Net-(IC2-MOT)") (class "Default")
      (node (ref "IC2") (pin "3") (pinfunction "MOT_3") (pintype "passive"))
      (node (ref "R9") (pin "2") (pinfunction "2_2") (pintype "passive"))
    )
    (net (code "25") (name "Net-(IC2-VD)") (class "Default")
      (node (ref "C15") (pin "2") (pinfunction "2_2") (pintype "passive"))
      (node (ref "IC2") (pin "4") (pinfunction "VD_4") (pintype "passive"))
      (node (ref "R3") (pin "1") (pinfunction "1_1") (pintype "passive"))
    )
    (net (code "26") (name "Net-(IC3-GATE)") (class "Default")
      (node (ref "IC3") (pin "5") (pinfunction "GATE_5") (pintype "passive"))
      (node (ref "R15") (pin "1") (pinfunction "1_1") (pintype "passive"))
    )
    (net (code "27") (name "Net-(IC3-MOT)") (class "Default")
      (node (ref "IC3") (pin "3") (pinfunction "MOT_3") (pintype "passive"))
      (node (ref "R20") (pin "2") (pinfunction "2_2") (pintype "passive"))
    )
    (net (code "28") (name "Net-(IC3-VD)") (class "Default")
      (node (ref "C29") (pin "2") (pinfunction "2_2") (pintype "passive"))
      (node (ref "IC3") (pin "4") (pinfunction "VD_4") (pintype "passive"))
      (node (ref "R13") (pin "1") (pinfunction "1_1") (pintype "passive"))
    )
    (net (code "29") (name "Net-(IC4-GATE)") (class "Default")
      (node (ref "IC4") (pin "5") (pinfunction "GATE_5") (pintype "passive"))
      (node (ref "R16") (pin "1") (pinfunction "1_1") (pintype "passive"))
    )
    (net (code "30") (name "Net-(IC4-MOT)") (class "Default")
      (node (ref "IC4") (pin "3") (pinfunction "MOT_3") (pintype "passive"))
      (node (ref "R21") (pin "2") (pinfunction "2_2") (pintype "passive"))
    )
    (net (code "31") (name "Net-(IC4-VD)") (class "Default")
      (node (ref "C30") (pin "2") (pinfunction "2_2") (pintype "passive"))
      (node (ref "IC4") (pin "4") (pinfunction "VD_4") (pintype "passive"))
      (node (ref "R14") (pin "1") (pinfunction "1_1") (pintype "passive"))
    )
    (net (code "32") (name "Net-(IC5-FB)") (class "Default")
      (node (ref "C37") (pin "1") (pinfunction "1_1") (pintype "passive"))
      (node (ref "IC5") (pin "4") (pinfunction "FB_4") (pintype "passive"))
      (node (ref "R25") (pin "1") (pinfunction "1_1") (pintype "passive"))
      (node (ref "R27") (pin "2") (pinfunction "2_2") (pintype "passive"))
    )
    (net (code "33") (name "Net-(IC6-+IN)") (class "Default")
      (node (ref "C31") (pin "2") (pinfunction "2_2") (pintype "passive"))
      (node (ref "C32") (pin "1") (pinfunction "1_1") (pintype "passive"))
      (node (ref "IC6") (pin "8") (pinfunction "+IN_8") (pintype "passive"))
      (node (ref "R24") (pin "1") (pinfunction "1_1") (pintype "passive"))
    )
    (net (code "34") (name "Net-(IC6--IN)") (class "Default")
      (node (ref "C31") (pin "1") (pinfunction "1_1") (pintype "passive"))
      (node (ref "C33") (pin "2") (pinfunction "2_2") (pintype "passive"))
      (node (ref "IC6") (pin "1") (pinfunction "-IN_1") (pintype "passive"))
      (node (ref "R23") (pin "1") (pinfunction "1_1") (pintype "passive"))
    )
    (net (code "35") (name "Net-(J1-Pad1)") (class "Default")
      (node (ref "J1") (pin "1") (pinfunction "1_1") (pintype "passive"))
      (node (ref "P2") (pin "2") (pinfunction "2_2") (pintype "passive"))
    )
    (net (code "36") (name "Net-(M1-G)") (class "Default")
      (node (ref "M1") (pin "4") (pinfunction "G_4") (pintype "passive"))
      (node (ref "R5") (pin "2") (pinfunction "2_2") (pintype "passive"))
      (node (ref "R7") (pin "2") (pinfunction "2_2") (pintype "passive"))
      (node (ref "TP2") (pin "1") (pinfunction "TP_1") (pintype "passive"))
    )
    (net (code "37") (name "Net-(M2-G)") (class "Default")
      (node (ref "M2") (pin "4") (pinfunction "G_4") (pintype "passive"))
      (node (ref "R4") (pin "2") (pinfunction "2_2") (pintype "passive"))
      (node (ref "R6") (pin "2") (pinfunction "2_2") (pintype "passive"))
      (node (ref "TP1") (pin "1") (pinfunction "TP_1") (pintype "passive"))
    )
    (net (code "38") (name "Net-(M3-G)") (class "Default")
      (node (ref "M3") (pin "4") (pinfunction "G_4") (pintype "passive"))
      (node (ref "R16") (pin "2") (pinfunction "2_2") (pintype "passive"))
      (node (ref "R19") (pin "2") (pinfunction "2_2") (pintype "passive"))
      (node (ref "TP8") (pin "1") (pinfunction "TP_1") (pintype "passive"))
    )
    (net (code "39") (name "Net-(M4-G)") (class "Default")
      (node (ref "M4") (pin "4") (pinfunction "G_4") (pintype "passive"))
      (node (ref "R15") (pin "2") (pinfunction "2_2") (pintype "passive"))
      (node (ref "R18") (pin "2") (pinfunction "2_2") (pintype "passive"))
      (node (ref "TP7") (pin "1") (pinfunction "TP_1") (pintype "passive"))
    )
    (net (code "40") (name "Net-(P1-Pad1)") (class "Default")
      (node (ref "P1") (pin "1") (pinfunction "1_1") (pintype "passive"))
      (node (ref "P1") (pin "S1") (pinfunction "SHIELD_S1") (pintype "passive"))
      (node (ref "P1") (pin "S2") (pinfunction "SHIELD_S2") (pintype "passive"))
      (node (ref "R1") (pin "1") (pinfunction "1_1") (pintype "passive"))
    )
    (net (code "41") (name "Net-(P4-Pad1)") (class "Default")
      (node (ref "P4") (pin "1") (pinfunction "1_1") (pintype "passive"))
      (node (ref "R28") (pin "2") (pinfunction "2_2") (pintype "passive"))
    )
    (net (code "42") (name "Net-(P5-Pad1)") (class "Default")
      (node (ref "P5") (pin "1") (pinfunction "1_1") (pintype "passive"))
      (node (ref "R30") (pin "1") (pinfunction "1_1") (pintype "passive"))
    )
    (net (code "43") (name "Net-(TP6-TP)") (class "Default")
      (node (ref "C22") (pin "1") (pinfunction "1_1") (pintype "passive"))
      (node (ref "TP6") (pin "1") (pinfunction "TP_1") (pintype "passive"))
      (node (ref "U1") (pin "1") (pinfunction "REF_1") (pintype "input"))
    )
    (net (code "44") (name "unconnected-(IC6-NC_1-Pad3)") (class "Default")
      (node (ref "IC6") (pin "3") (pinfunction "NC_1_3") (pintype "passive+no_connect"))
    )
    (net (code "45") (name "unconnected-(IC6-NC_2-Pad4)") (class "Default")
      (node (ref "IC6") (pin "4") (pinfunction "NC_2_4") (pintype "passive+no_connect"))
    )
    (net (code "46") (name "unconnected-(IC6-NC_3-Pad7)") (class "Default")
      (node (ref "IC6") (pin "7") (pinfunction "NC_3_7") (pintype "passive+no_connect"))
    )
    (net (code "47") (name "unconnected-(J1-Pad2)") (class "Default")
      (node (ref "J1") (pin "2") (pinfunction "2_2") (pintype "passive+no_connect"))
    )
    (net (code "48") (name "unconnected-(J1-Pad3)") (class "Default")
      (node (ref "J1") (pin "3") (pinfunction "3_3") (pintype "passive+no_connect"))
    )
    (net (code "49") (name "unconnected-(J1-Pad4)") (class "Default")
      (node (ref "J1") (pin "4") (pinfunction "4_4") (pintype "passive+no_connect"))
    )
    (net (code "50") (name "unconnected-(J1-Pad5)") (class "Default")
      (node (ref "J1") (pin "5") (pinfunction "5_5") (pintype "passive+no_connect"))
    )
    (net (code "51") (name "unconnected-(J1-Pad6)") (class "Default")
      (node (ref "J1") (pin "6") (pinfunction "6_6") (pintype "passive+no_connect"))
    )
    (net (code "52") (name "unconnected-(J1-Pad7)") (class "Default")
      (node (ref "J1") (pin "7") (pinfunction "7_7") (pintype "passive+no_connect"))
    )
    (net (code "53") (name "unconnected-(J1-Pad10)") (class "Default")
      (node (ref "J1") (pin "10") (pinfunction "10_10") (pintype "passive+no_connect"))
    )
    (net (code "54") (name "unconnected-(J2-Pad2)") (class "Default")
      (node (ref "J2") (pin "2") (pinfunction "2_2") (pintype "passive+no_connect"))
    )
    (net (code "55") (name "unconnected-(J2-Pad5)") (class "Default")
      (node (ref "J2") (pin "5") (pinfunction "5_5") (pintype "passive+no_connect"))
    )
    (net (code "56") (name "unconnected-(J2-Pad6)") (class "Default")
      (node (ref "J2") (pin "6") (pinfunction "6_6") (pintype "passive+no_connect"))
    )
    (net (code "57") (name "unconnected-(J2-Pad7)") (class "Default")
      (node (ref "J2") (pin "7") (pinfunction "7_7") (pintype "passive+no_connect"))
    )
    (net (code "58") (name "unconnected-(J2-Pad8)") (class "Default")
      (node (ref "J2") (pin "8") (pinfunction "8_8") (pintype "passive+no_connect"))
    )
    (net (code "59") (name "unconnected-(J2-Pad9)") (class "Default")
      (node (ref "J2") (pin "9") (pinfunction "9_9") (pintype "passive+no_connect"))
    )
    (net (code "60") (name "unconnected-(J2-Pad10)") (class "Default")
      (node (ref "J2") (pin "10") (pinfunction "10_10") (pintype "passive+no_connect"))
    )
    (net (code "61") (name "unconnected-(M5-Pad1)") (class "Default")
      (node (ref "M5") (pin "1") (pinfunction "1_1") (pintype "passive+no_connect"))
    )
    (net (code "62") (name "unconnected-(M6-Pad1)") (class "Default")
      (node (ref "M6") (pin "1") (pinfunction "1_1") (pintype "passive+no_connect"))
    )
    (net (code "63") (name "unconnected-(M7-Pad1)") (class "Default")
      (node (ref "M7") (pin "1") (pinfunction "1_1") (pintype "passive+no_connect"))
    )
    (net (code "64") (name "unconnected-(M8-Pad1)") (class "Default")
      (node (ref "M8") (pin "1") (pinfunction "1_1") (pintype "passive+no_connect"))
    )
    (net (code "65") (name "unconnected-(P3-SHIELD-PadS1)") (class "Default")
      (node (ref "P3") (pin "S1") (pinfunction "SHIELD_S1") (pintype "passive+no_connect"))
    )
    (net (code "66") (name "unconnected-(P3-SHIELD-PadS2)") (class "Default")
      (node (ref "P3") (pin "S2") (pinfunction "SHIELD_S2") (pintype "passive+no_connect"))
    )
    (net (code "67") (name "unconnected-(R28-Pad3)") (class "Default")
      (node (ref "R28") (pin "3") (pinfunction "3_3") (pintype "passive+no_connect"))
    )
    (net (code "68") (name "unconnected-(R30-Pad3)") (class "Default")
      (node (ref "R30") (pin "3") (pinfunction "3_3") (pintype "passive+no_connect"))
    )
  )
)
